# ESP32-Proto2-LayoutA.net
KiCad netlist of a schematic drawn in EAGLE
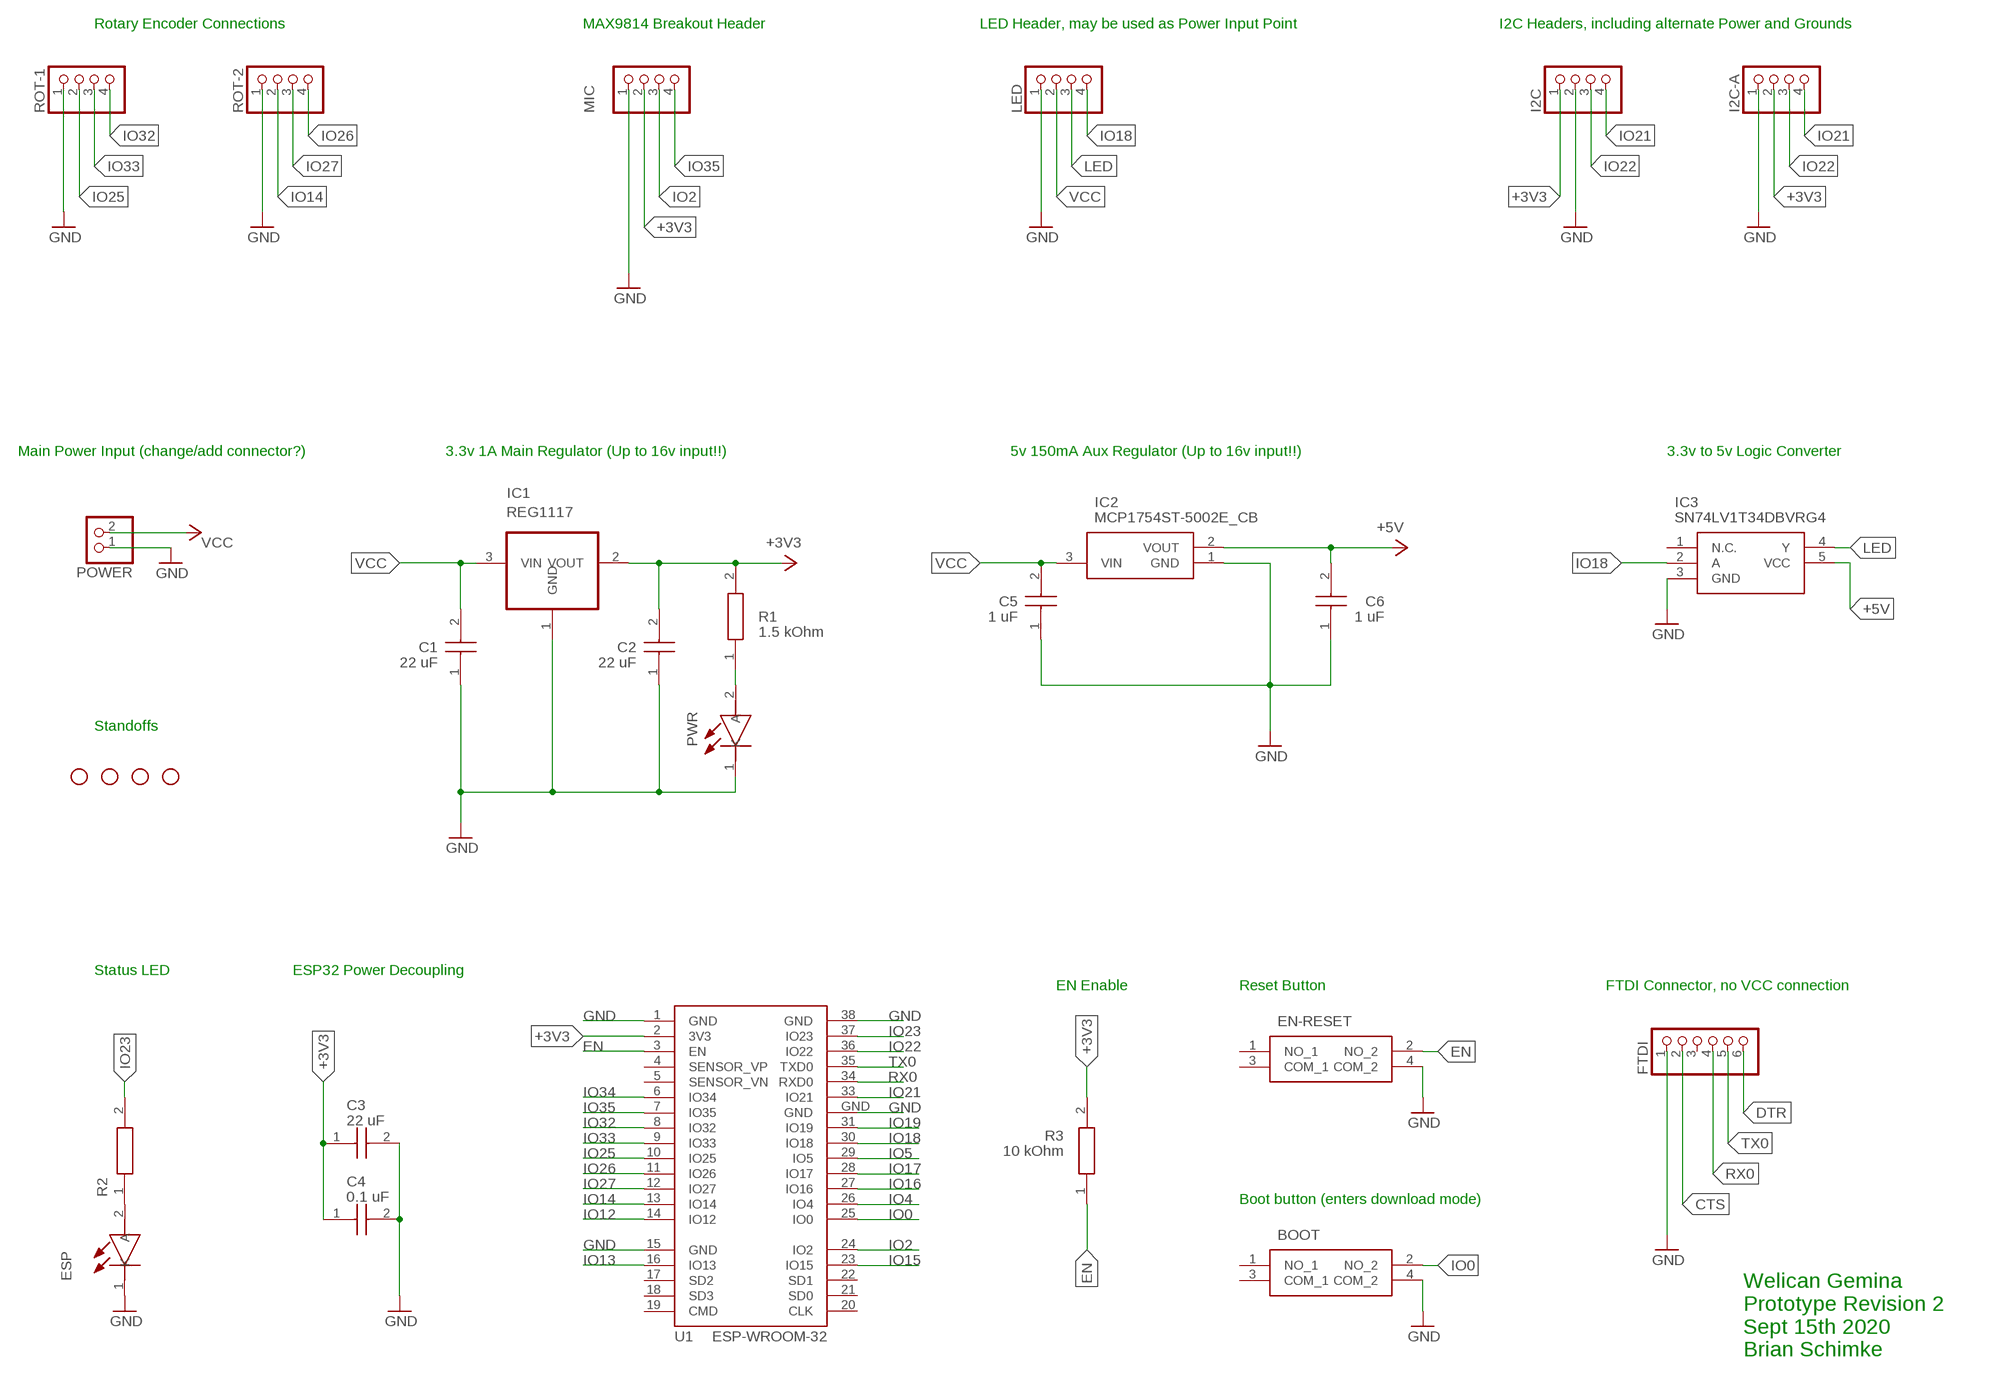
[diagram p0: schematic, sheet 1]

(export (version "E")
  (design (tool "Eeschema 10.0.6"))
  (components
    (comp (ref "BOOT")
      (value "PTS647SK70SMTR2LFS")
      (footprint "eagle-import:PTS647SK70SMTR2LFS")
      (fields (field (name "MOUSER_PART_NUMBER") "611-PTS647SK70SMTR2L"))
      (libsource (lib "eagle-import") (part "PTS647SK70SMTR2LFS"))
    )
    (comp (ref "C1")
      (value "22 uF")
      (footprint "eagle-import:CAPC3216X180N")
      (fields
        (field (name "MANUFACTURER_PART_NUMBER") "C1206C226M4PACTU")
        (field (name "MOUSER_PART_NUMBER") "80-C1206C226M4P")
      )
      (libsource (lib "eagle-import") (part "C1206C226M4PACTU"))
    )
    (comp (ref "C2")
      (value "22 uF")
      (footprint "eagle-import:CAPC3216X180N")
      (fields
        (field (name "MANUFACTURER_PART_NUMBER") "C1206C226M4PACTU")
        (field (name "MOUSER_PART_NUMBER") "80-C1206C226M4P")
      )
      (libsource (lib "eagle-import") (part "C1206C226M4PACTU"))
    )
    (comp (ref "C3")
      (value "22 uF")
      (footprint "eagle-import:CAPC3216X180N")
      (fields
        (field (name "MANUFACTURER_PART_NUMBER") "C1206C226M4PACTU")
        (field (name "MOUSER_PART_NUMBER") "80-C1206C226M4P")
      )
      (libsource (lib "eagle-import") (part "C1206C226M4PACTU"))
    )
    (comp (ref "C4")
      (value "0.1 uF")
      (footprint "eagle-import:CAPC3216X180N")
      (fields
        (field (name "MANUFACTURER_PART_NUMBER") "C1206C226M4PACTU")
        (field (name "MOUSER_PART_NUMBER") "80-C1206C226M4P")
      )
      (libsource (lib "eagle-import") (part "C1206C226M4PACTU"))
    )
    (comp (ref "C5")
      (value "1 uF")
      (footprint "eagle-import:CAPC3216X180N")
      (fields
        (field (name "MANUFACTURER_PART_NUMBER") "C1206C226M4PACTU")
        (field (name "MOUSER_PART_NUMBER") "80-C1206C226M4P")
      )
      (libsource (lib "eagle-import") (part "C1206C226M4PACTU"))
    )
    (comp (ref "C6")
      (value "1 uF")
      (footprint "eagle-import:CAPC3216X180N")
      (fields
        (field (name "MANUFACTURER_PART_NUMBER") "C1206C226M4PACTU")
        (field (name "MOUSER_PART_NUMBER") "80-C1206C226M4P")
      )
      (libsource (lib "eagle-import") (part "C1206C226M4PACTU"))
    )
    (comp (ref "EN-RESET")
      (value "PTS647SK70SMTR2LFS")
      (footprint "eagle-import:PTS647SK70SMTR2LFS")
      (fields (field (name "MOUSER_PART_NUMBER") "611-PTS647SK70SMTR2L"))
      (libsource (lib "eagle-import") (part "PTS647SK70SMTR2LFS"))
    )
    (comp (ref "ESP")
      (value "150120AS75000")
      (footprint "eagle-import:LEDSC320X160X78-2N")
      (fields (field (name "MOUSER_PART_NUMBER") "710-150120AS75000"))
      (libsource (lib "eagle-import") (part "150120AS75000"))
    )
    (comp (ref "FTDI")
      (value "PINHD-1X6")
      (footprint "eagle-import:1X06")
      (libsource (lib "eagle-import") (part "PINHD-1X6"))
    )
    (comp (ref "H1")
      (value "STAND-OFF")
      (footprint "eagle-import:STAND-OFF")
      (libsource (lib "eagle-import") (part "STAND-OFF"))
    )
    (comp (ref "H2")
      (value "STAND-OFF")
      (footprint "eagle-import:STAND-OFF")
      (libsource (lib "eagle-import") (part "STAND-OFF"))
    )
    (comp (ref "H3")
      (value "STAND-OFF")
      (footprint "eagle-import:STAND-OFF")
      (libsource (lib "eagle-import") (part "STAND-OFF"))
    )
    (comp (ref "H4")
      (value "STAND-OFF")
      (footprint "eagle-import:STAND-OFF")
      (libsource (lib "eagle-import") (part "STAND-OFF"))
    )
    (comp (ref "I2C")
      (value "PINHD-1X4")
      (footprint "eagle-import:1X04")
      (libsource (lib "eagle-import") (part "PINHD-1X4"))
    )
    (comp (ref "I2C-A")
      (value "PINHD-1X4")
      (footprint "eagle-import:1X04")
      (libsource (lib "eagle-import") (part "PINHD-1X4"))
    )
    (comp (ref "IC1")
      (value "REG1117")
      (footprint "eagle-import:SOT223")
      (libsource (lib "eagle-import") (part "REG1117"))
    )
    (comp (ref "IC2")
      (value "MCP1754ST-5002E_CB")
      (footprint "eagle-import:SOT95P255X145-3N")
      (fields
        (field (name "MANUFACTURER_PART_NUMBER") "MCP1754ST-5002E/CB")
        (field (name "MOUSER_PART_NUMBER") "579-MCP1754T-5002ECB")
      )
      (libsource (lib "eagle-import") (part "MCP1754ST-5002E_CB"))
    )
    (comp (ref "IC3")
      (value "SN74LV1T34DBVRG4")
      (footprint "eagle-import:SOT95P280X145-5N")
      (fields (field (name "MOUSER_PART_NUMBER") "595-SN74LV1T34DBVRG4"))
      (libsource (lib "eagle-import") (part "SN74LV1T34DBVRG4"))
    )
    (comp (ref "LED")
      (value "PINHD-1X4")
      (footprint "eagle-import:1X04")
      (libsource (lib "eagle-import") (part "PINHD-1X4"))
    )
    (comp (ref "MIC")
      (value "PINHD-1X4")
      (footprint "eagle-import:1X04")
      (libsource (lib "eagle-import") (part "PINHD-1X4"))
    )
    (comp (ref "POWER")
      (value "PINHD-1X2")
      (footprint "eagle-import:1X02")
      (libsource (lib "eagle-import") (part "PINHD-1X2"))
    )
    (comp (ref "PWR")
      (value "150120AS75000")
      (footprint "eagle-import:LEDSC320X160X78-2N")
      (fields (field (name "MOUSER_PART_NUMBER") "710-150120AS75000"))
      (libsource (lib "eagle-import") (part "150120AS75000"))
    )
    (comp (ref "R1")
      (value "1.5 kOhm")
      (footprint "eagle-import:RESC3216X60N")
      (fields
        (field (name "MANUFACTURER_PART_NUMBER") "CRCW12061K00FKEB")
        (field (name "MOUSER_PART_NUMBER") "71-CRCW12061K00FKEB")
      )
      (libsource (lib "eagle-import") (part "CRCW12061K00FKEB"))
    )
    (comp (ref "R2")
      (value "CRCW12061K00FKEB")
      (footprint "eagle-import:RESC3216X60N")
      (fields (field (name "MOUSER_PART_NUMBER") "71-CRCW12061K00FKEB"))
      (libsource (lib "eagle-import") (part "CRCW12061K00FKEB"))
    )
    (comp (ref "R3")
      (value "10 kOhm")
      (footprint "eagle-import:RESC3216X60N")
      (fields
        (field (name "MANUFACTURER_PART_NUMBER") "CRCW12061K00FKEB")
        (field (name "MOUSER_PART_NUMBER") "71-CRCW12061K00FKEB")
      )
      (libsource (lib "eagle-import") (part "CRCW12061K00FKEB"))
    )
    (comp (ref "ROT-1")
      (value "PINHD-1X4")
      (footprint "eagle-import:1X04")
      (libsource (lib "eagle-import") (part "PINHD-1X4"))
    )
    (comp (ref "ROT-2")
      (value "PINHD-1X4")
      (footprint "eagle-import:1X04")
      (libsource (lib "eagle-import") (part "PINHD-1X4"))
    )
    (comp (ref "U1")
      (value "ESP-WROOM-32")
      (footprint "eagle-import:ESP-WROOM-32")
      (libsource (lib "eagle-import") (part "ESP-WROOM-32"))
    )
  )
  (nets
    (net (code "1") (name "+3V3") (class "Default")
      (node (ref "C2") (pin "2") (pinfunction "2_2") (pintype "bidirectional"))
      (node (ref "C3") (pin "1") (pinfunction "1_1") (pintype "bidirectional"))
      (node (ref "C4") (pin "1") (pinfunction "1_1") (pintype "bidirectional"))
      (node (ref "I2C") (pin "1") (pinfunction "1_1") (pintype "passive"))
      (node (ref "I2C-A") (pin "2") (pinfunction "2_2") (pintype "passive"))
      (node (ref "IC1") (pin "2") (pinfunction "VOUT_2") (pintype "output"))
      (node (ref "MIC") (pin "2") (pinfunction "2_2") (pintype "passive"))
      (node (ref "R1") (pin "2") (pinfunction "2_2") (pintype "bidirectional"))
      (node (ref "R3") (pin "2") (pinfunction "2_2") (pintype "bidirectional"))
      (node (ref "U1") (pin "2") (pinfunction "3V3_2") (pintype "power_in"))
    )
    (net (code "2") (name "+5V") (class "Default")
      (node (ref "C6") (pin "2") (pinfunction "2_2") (pintype "bidirectional"))
      (node (ref "IC2") (pin "2") (pinfunction "VOUT_2") (pintype "bidirectional"))
      (node (ref "IC3") (pin "5") (pinfunction "VCC_5") (pintype "bidirectional"))
    )
    (net (code "3") (name "/IO4") (class "Default")
      (node (ref "U1") (pin "26") (pinfunction "IO4_26") (pintype "bidirectional"))
    )
    (net (code "4") (name "/IO5") (class "Default")
      (node (ref "U1") (pin "29") (pinfunction "IO5_29") (pintype "bidirectional"))
    )
    (net (code "5") (name "/IO12") (class "Default")
      (node (ref "U1") (pin "14") (pinfunction "IO12_14") (pintype "bidirectional"))
    )
    (net (code "6") (name "/IO13") (class "Default")
      (node (ref "U1") (pin "16") (pinfunction "IO13_16") (pintype "bidirectional"))
    )
    (net (code "7") (name "/IO15") (class "Default")
      (node (ref "U1") (pin "23") (pinfunction "IO15_23") (pintype "bidirectional"))
    )
    (net (code "8") (name "/IO16") (class "Default")
      (node (ref "U1") (pin "27") (pinfunction "IO16_27") (pintype "bidirectional"))
    )
    (net (code "9") (name "/IO17") (class "Default")
      (node (ref "U1") (pin "28") (pinfunction "IO17_28") (pintype "bidirectional"))
    )
    (net (code "10") (name "/IO19") (class "Default")
      (node (ref "U1") (pin "31") (pinfunction "IO19_31") (pintype "bidirectional"))
    )
    (net (code "11") (name "/IO34") (class "Default")
      (node (ref "U1") (pin "6") (pinfunction "IO34_6") (pintype "bidirectional"))
    )
    (net (code "12") (name "CTS") (class "Default")
      (node (ref "FTDI") (pin "2") (pinfunction "2_2") (pintype "passive"))
    )
    (net (code "13") (name "DTR") (class "Default")
      (node (ref "FTDI") (pin "6") (pinfunction "6_6") (pintype "passive"))
    )
    (net (code "14") (name "EN") (class "Default")
      (node (ref "EN-RESET") (pin "2") (pinfunction "NO_2_2") (pintype "bidirectional"))
      (node (ref "R3") (pin "1") (pinfunction "1_1") (pintype "bidirectional"))
      (node (ref "U1") (pin "3") (pinfunction "EN_3") (pintype "input"))
    )
    (net (code "15") (name "GND") (class "Default")
      (node (ref "BOOT") (pin "4") (pinfunction "COM_2_4") (pintype "bidirectional"))
      (node (ref "C1") (pin "1") (pinfunction "1_1") (pintype "bidirectional"))
      (node (ref "C2") (pin "1") (pinfunction "1_1") (pintype "bidirectional"))
      (node (ref "C3") (pin "2") (pinfunction "2_2") (pintype "bidirectional"))
      (node (ref "C4") (pin "2") (pinfunction "2_2") (pintype "bidirectional"))
      (node (ref "C5") (pin "1") (pinfunction "1_1") (pintype "bidirectional"))
      (node (ref "C6") (pin "1") (pinfunction "1_1") (pintype "bidirectional"))
      (node (ref "EN-RESET") (pin "4") (pinfunction "COM_2_4") (pintype "bidirectional"))
      (node (ref "ESP") (pin "1") (pinfunction "K_1") (pintype "bidirectional"))
      (node (ref "FTDI") (pin "1") (pinfunction "1_1") (pintype "passive"))
      (node (ref "I2C") (pin "2") (pinfunction "2_2") (pintype "passive"))
      (node (ref "I2C-A") (pin "1") (pinfunction "1_1") (pintype "passive"))
      (node (ref "IC1") (pin "1") (pinfunction "GND_1") (pintype "power_in"))
      (node (ref "IC2") (pin "1") (pinfunction "GND_1") (pintype "bidirectional"))
      (node (ref "IC3") (pin "3") (pinfunction "GND_3") (pintype "bidirectional"))
      (node (ref "LED") (pin "1") (pinfunction "1_1") (pintype "passive"))
      (node (ref "MIC") (pin "1") (pinfunction "1_1") (pintype "passive"))
      (node (ref "POWER") (pin "1") (pinfunction "1_1") (pintype "passive"))
      (node (ref "PWR") (pin "1") (pinfunction "K_1") (pintype "bidirectional"))
      (node (ref "ROT-1") (pin "1") (pinfunction "1_1") (pintype "passive"))
      (node (ref "ROT-2") (pin "1") (pinfunction "1_1") (pintype "passive"))
      (node (ref "U1") (pin "1") (pinfunction "GND_1") (pintype "power_in"))
      (node (ref "U1") (pin "15") (pinfunction "GND_15") (pintype "power_in"))
      (node (ref "U1") (pin "38") (pinfunction "GND_38") (pintype "power_in"))
      (node (ref "U1") (pin "GND") (pinfunction "GND_GND") (pintype "power_in"))
    )
    (net (code "16") (name "IO0") (class "Default")
      (node (ref "BOOT") (pin "2") (pinfunction "NO_2_2") (pintype "bidirectional"))
      (node (ref "U1") (pin "25") (pinfunction "IO0_25") (pintype "bidirectional"))
    )
    (net (code "17") (name "IO2") (class "Default")
      (node (ref "MIC") (pin "3") (pinfunction "3_3") (pintype "passive"))
      (node (ref "U1") (pin "24") (pinfunction "IO2_24") (pintype "bidirectional"))
    )
    (net (code "18") (name "IO14") (class "Default")
      (node (ref "ROT-2") (pin "2") (pinfunction "2_2") (pintype "passive"))
      (node (ref "U1") (pin "13") (pinfunction "IO14_13") (pintype "bidirectional"))
    )
    (net (code "19") (name "IO18") (class "Default")
      (node (ref "IC3") (pin "2") (pinfunction "A_2") (pintype "bidirectional"))
      (node (ref "LED") (pin "4") (pinfunction "4_4") (pintype "passive"))
      (node (ref "U1") (pin "30") (pinfunction "IO18_30") (pintype "bidirectional"))
    )
    (net (code "20") (name "IO21") (class "Default")
      (node (ref "I2C") (pin "4") (pinfunction "4_4") (pintype "passive"))
      (node (ref "I2C-A") (pin "4") (pinfunction "4_4") (pintype "passive"))
      (node (ref "U1") (pin "33") (pinfunction "IO21_33") (pintype "bidirectional"))
    )
    (net (code "21") (name "IO22") (class "Default")
      (node (ref "I2C") (pin "3") (pinfunction "3_3") (pintype "passive"))
      (node (ref "I2C-A") (pin "3") (pinfunction "3_3") (pintype "passive"))
      (node (ref "U1") (pin "36") (pinfunction "IO22_36") (pintype "bidirectional"))
    )
    (net (code "22") (name "IO23") (class "Default")
      (node (ref "R2") (pin "2") (pinfunction "2_2") (pintype "bidirectional"))
      (node (ref "U1") (pin "37") (pinfunction "IO23_37") (pintype "bidirectional"))
    )
    (net (code "23") (name "IO25") (class "Default")
      (node (ref "ROT-1") (pin "2") (pinfunction "2_2") (pintype "passive"))
      (node (ref "U1") (pin "10") (pinfunction "IO25_10") (pintype "bidirectional"))
    )
    (net (code "24") (name "IO26") (class "Default")
      (node (ref "ROT-2") (pin "4") (pinfunction "4_4") (pintype "passive"))
      (node (ref "U1") (pin "11") (pinfunction "IO26_11") (pintype "bidirectional"))
    )
    (net (code "25") (name "IO27") (class "Default")
      (node (ref "ROT-2") (pin "3") (pinfunction "3_3") (pintype "passive"))
      (node (ref "U1") (pin "12") (pinfunction "IO27_12") (pintype "bidirectional"))
    )
    (net (code "26") (name "IO32") (class "Default")
      (node (ref "ROT-1") (pin "4") (pinfunction "4_4") (pintype "passive"))
      (node (ref "U1") (pin "8") (pinfunction "IO32_8") (pintype "bidirectional"))
    )
    (net (code "27") (name "IO33") (class "Default")
      (node (ref "ROT-1") (pin "3") (pinfunction "3_3") (pintype "passive"))
      (node (ref "U1") (pin "9") (pinfunction "IO33_9") (pintype "bidirectional"))
    )
    (net (code "28") (name "IO35") (class "Default")
      (node (ref "MIC") (pin "4") (pinfunction "4_4") (pintype "passive"))
      (node (ref "U1") (pin "7") (pinfunction "IO35_7") (pintype "bidirectional"))
    )
    (net (code "29") (name "LED") (class "Default")
      (node (ref "IC3") (pin "4") (pinfunction "Y_4") (pintype "bidirectional"))
      (node (ref "LED") (pin "3") (pinfunction "3_3") (pintype "passive"))
    )
    (net (code "30") (name "Net-(ESP-A)") (class "Default")
      (node (ref "ESP") (pin "2") (pinfunction "A_2") (pintype "bidirectional"))
      (node (ref "R2") (pin "1") (pinfunction "1_1") (pintype "bidirectional"))
    )
    (net (code "31") (name "Net-(PWR-A)") (class "Default")
      (node (ref "PWR") (pin "2") (pinfunction "A_2") (pintype "bidirectional"))
      (node (ref "R1") (pin "1") (pinfunction "1_1") (pintype "bidirectional"))
    )
    (net (code "32") (name "RX0") (class "Default")
      (node (ref "FTDI") (pin "4") (pinfunction "4_4") (pintype "passive"))
      (node (ref "U1") (pin "34") (pinfunction "RXD0_34") (pintype "bidirectional"))
    )
    (net (code "33") (name "TX0") (class "Default")
      (node (ref "FTDI") (pin "5") (pinfunction "5_5") (pintype "passive"))
      (node (ref "U1") (pin "35") (pinfunction "TXD0_35") (pintype "bidirectional"))
    )
    (net (code "34") (name "VCC") (class "Default")
      (node (ref "C1") (pin "2") (pinfunction "2_2") (pintype "bidirectional"))
      (node (ref "C5") (pin "2") (pinfunction "2_2") (pintype "bidirectional"))
      (node (ref "IC1") (pin "3") (pinfunction "VIN_3") (pintype "input"))
      (node (ref "IC2") (pin "3") (pinfunction "VIN_3") (pintype "bidirectional"))
      (node (ref "LED") (pin "2") (pinfunction "2_2") (pintype "passive"))
      (node (ref "POWER") (pin "2") (pinfunction "2_2") (pintype "passive"))
    )
    (net (code "35") (name "unconnected-(BOOT-COM_1-Pad3)") (class "Default")
      (node (ref "BOOT") (pin "3") (pinfunction "COM_1_3") (pintype "bidirectional"))
    )
    (net (code "36") (name "unconnected-(BOOT-NO_1-Pad1)") (class "Default")
      (node (ref "BOOT") (pin "1") (pinfunction "NO_1_1") (pintype "bidirectional"))
    )
    (net (code "37") (name "unconnected-(EN-RESET-COM_1-Pad3)") (class "Default")
      (node (ref "EN-RESET") (pin "3") (pinfunction "COM_1_3") (pintype "bidirectional"))
    )
    (net (code "38") (name "unconnected-(EN-RESET-NO_1-Pad1)") (class "Default")
      (node (ref "EN-RESET") (pin "1") (pinfunction "NO_1_1") (pintype "bidirectional"))
    )
    (net (code "39") (name "unconnected-(FTDI-Pad3)") (class "Default")
      (node (ref "FTDI") (pin "3") (pinfunction "3_3") (pintype "passive"))
    )
    (net (code "40") (name "unconnected-(IC3-N.C.-Pad1)") (class "Default")
      (node (ref "IC3") (pin "1") (pinfunction "N.C._1") (pintype "no_connect"))
    )
    (net (code "41") (name "unconnected-(U1-CLK-Pad20)") (class "Default")
      (node (ref "U1") (pin "20") (pinfunction "CLK_20") (pintype "bidirectional"))
    )
    (net (code "42") (name "unconnected-(U1-CMD-Pad19)") (class "Default")
      (node (ref "U1") (pin "19") (pinfunction "CMD_19") (pintype "bidirectional"))
    )
    (net (code "43") (name "unconnected-(U1-SD0-Pad21)") (class "Default")
      (node (ref "U1") (pin "21") (pinfunction "SD0_21") (pintype "bidirectional"))
    )
    (net (code "44") (name "unconnected-(U1-SD1-Pad22)") (class "Default")
      (node (ref "U1") (pin "22") (pinfunction "SD1_22") (pintype "bidirectional"))
    )
    (net (code "45") (name "unconnected-(U1-SD2-Pad17)") (class "Default")
      (node (ref "U1") (pin "17") (pinfunction "SD2_17") (pintype "bidirectional"))
    )
    (net (code "46") (name "unconnected-(U1-SD3-Pad18)") (class "Default")
      (node (ref "U1") (pin "18") (pinfunction "SD3_18") (pintype "bidirectional"))
    )
    (net (code "47") (name "unconnected-(U1-SENSOR_VN-Pad5)") (class "Default")
      (node (ref "U1") (pin "5") (pinfunction "SENSOR_VN_5") (pintype "bidirectional"))
    )
    (net (code "48") (name "unconnected-(U1-SENSOR_VP-Pad4)") (class "Default")
      (node (ref "U1") (pin "4") (pinfunction "SENSOR_VP_4") (pintype "bidirectional"))
    )
  )
)
